# Sheet1.net
KiCad netlist of a schematic drawn in Altium Designer
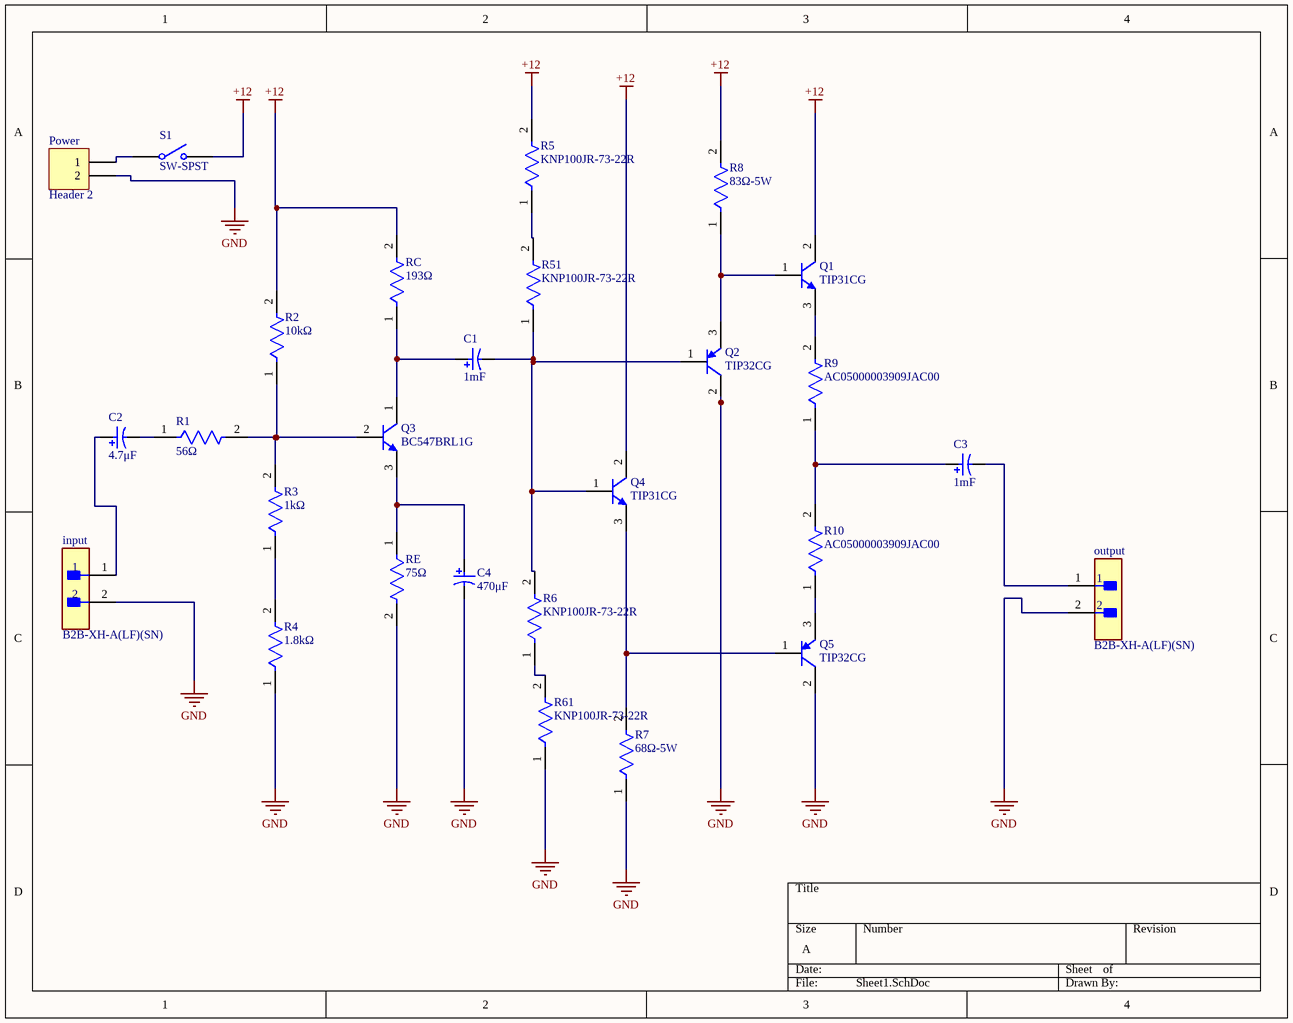
[diagram p0: Sheet1.SchDoc]

(export (version "E")
  (design (tool "Eeschema 10.0.6"))
  (components
    (comp (ref "C1")
      (value "1mF")
      (footprint "PNSC-EEU-EE2G100-2_V")
      (fields (field (name "PARTNUMBER") "EEU-EE2G100") (field (name "MANUFACTURER") "Panasonic"))
      (libsource (lib "Altium Content Vault") (part "PNSC-CAP-P-2"))
    )
    (comp (ref "C2")
      (value "4.7μF")
      (footprint "CAPPR55-200-1100X500X1200")
      (description "Aluminum Electrolytic Capacitor, 2.2 uF, +/- 20%, 50 V, -40 to 85 degC, 2-Pin THD, RoHS, Bulk")
      (fields (field (name "VOLTAGE") "50V") (field (name "MANUFACTURER") "Panasonic"))
      (libsource (lib "Altium Content Vault") (part "CAP-P-2"))
    )
    (comp (ref "C3")
      (value "1mF")
      (footprint "PNSC-EEU-EE2G100-2_V")
      (fields (field (name "PARTNUMBER") "EEU-EE2G100") (field (name "MANUFACTURER") "Panasonic"))
      (libsource (lib "Altium Content Vault") (part "PNSC-CAP-P-2"))
    )
    (comp (ref "C4")
      (value "470μF")
      (footprint "CAPPR55-200-1100X500X1200")
      (description "Aluminum Electrolytic Capacitor, 22 uF, +/- 20%, 50 V, -40 to 85 degC, 2-Pin THD, RoHS, Bulk")
      (fields (field (name "VOLTAGE") "50V") (field (name "MANUFACTURER") "Panasonic"))
      (libsource (lib "Altium Content Vault") (part "CAP-P-2"))
    )
    (comp (ref "input")
      (value "B2B-XH-A(LF)(SN)")
      (footprint "FP-B2B-XH-A_LF_SN-MFG")
      (description "CONN HEADER VERT 2POS 2.5MM")
      (libsource (lib "") (part "3bc925449376181038e59eaffc5286c_1"))
    )
    (comp (ref "output")
      (value "B2B-XH-A(LF)(SN)")
      (footprint "FP-B2B-XH-A_LF_SN-MFG")
      (description "CONN HEADER VERT 2POS 2.5MM")
      (libsource (lib "Altium Content Vault") (part "3bc925449376181038e59eaffc5286c"))
    )
    (comp (ref "Power")
      (value "Header 2")
      (footprint "HDR1X2")
      (description "Header, 2-Pin")
      (fields (field (name "PUBLISHER") "Altium Limited"))
      (libsource (lib "Miscellaneous Connectors") (part "Header 2"))
    )
    (comp (ref "Q1")
      (value "TIP31CG")
      (footprint "ONSC-TO-220-3-221A-09")
      (description "Complementary Silicon Plastic Power Transistor, 3-Pin TO-220, Pb-Free, Tube")
      (fields (field (name "MANUFACTURER") "On Semiconductor"))
      (libsource (lib "Altium Content Vault") (part "ONSC-NPN-B1C2E3-3_C"))
    )
    (comp (ref "Q2")
      (value "TIP32CG")
      (footprint "ONSC-TO-220-3-221A-09")
      (description "Complementary Silicon Plastic Power Transistor, 3-Pin TO-220, Pb-Free, Tube")
      (fields (field (name "MANUFACTURER") "On Semiconductor"))
      (libsource (lib "Altium Content Vault") (part "ONSC-PNP-B1C2E3-3"))
    )
    (comp (ref "Q3")
      (value "BC547BRL1G")
      (footprint "ONSC-TO-92-3-29-11_AM_BL")
      (description "Amplifier Transistor, NPN Silicon, 3-Pin TO-92, Pb-Free, Tape and Reel")
      (fields (field (name "MANUFACTURER") "On Semiconductor"))
      (libsource (lib "Altium Content Vault") (part "ONSC-NPN-C1B2E3-3"))
    )
    (comp (ref "Q4")
      (value "TIP31CG")
      (footprint "ONSC-TO-220-3-221A-09")
      (description "Complementary Silicon Plastic Power Transistor, 3-Pin TO-220, Pb-Free, Tube")
      (fields (field (name "MANUFACTURER") "On Semiconductor"))
      (libsource (lib "Altium Content Vault") (part "ONSC-NPN-B1C2E3-3_C"))
    )
    (comp (ref "Q5")
      (value "TIP32CG")
      (footprint "ONSC-TO-220-3-221A-09")
      (description "Complementary Silicon Plastic Power Transistor, 3-Pin TO-220, Pb-Free, Tube")
      (fields (field (name "MANUFACTURER") "On Semiconductor"))
      (libsource (lib "Altium Content Vault") (part "ONSC-PNP-B1C2E3-3"))
    )
    (comp (ref "R1")
      (value "56Ω")
      (footprint "FP-MRS25-MFG")
      (description "RES 1.1K OHM 0.6W 1% AXIAL")
      (fields
        (field (name "MANUFACTURER") "Vishay BC Components")
        (field (name "OCTOPART") "https://octopart.com/mrs25000c1101fct00-vishay-43740214")
      )
      (libsource (lib "Altium Content Vault") (part "1029c3af85768c4190bb7ad29bc67b5"))
    )
    (comp (ref "R2")
      (value "10kΩ")
      (footprint "FP-MRS25-MFG")
      (description "RES 1.1K OHM 0.6W 1% AXIAL")
      (fields
        (field (name "MANUFACTURER") "Vishay BC Components")
        (field (name "OCTOPART") "https://octopart.com/mrs25000c1101fct00-vishay-43740214")
      )
      (libsource (lib "Altium Content Vault") (part "1029c3af85768c4190bb7ad29bc67b5"))
    )
    (comp (ref "R3")
      (value "1kΩ")
      (footprint "FP-MRS25-MFG")
      (description "RES 1.1K OHM 0.6W 1% AXIAL")
      (fields
        (field (name "MANUFACTURER") "Vishay BC Components")
        (field (name "OCTOPART") "https://octopart.com/mrs25000c1101fct00-vishay-43740214")
      )
      (libsource (lib "Altium Content Vault") (part "1029c3af85768c4190bb7ad29bc67b5"))
    )
    (comp (ref "R4")
      (value "1.8kΩ")
      (footprint "FP-MRS25-MFG")
      (description "RES 1.1K OHM 0.6W 1% AXIAL")
      (fields
        (field (name "MANUFACTURER") "Vishay BC Components")
        (field (name "OCTOPART") "https://octopart.com/mrs25000c1101fct00-vishay-43740214")
      )
      (libsource (lib "Altium Content Vault") (part "1029c3af85768c4190bb7ad29bc67b5"))
    )
    (comp (ref "R5")
      (value "KNP100JR-73-22R")
      (footprint "FP-KNP100-MFG")
      (description "22 Ohms ±5% 1W Through Hole Resistor Axial Flame Retardant Coating, Safety Wirewound")
      (fields (field (name "OCTOPART") "https://octopart.com/knp100jr-73-22r-yageo-19031610"))
      (libsource (lib "Altium Content Vault") (part "1029c3af85768c4190bb7ad29bc67b5"))
    )
    (comp (ref "R6")
      (value "KNP100JR-73-22R")
      (footprint "FP-KNP100-MFG")
      (description "22 Ohms ±5% 1W Through Hole Resistor Axial Flame Retardant Coating, Safety Wirewound")
      (fields (field (name "OCTOPART") "https://octopart.com/knp100jr-73-22r-yageo-19031610"))
      (libsource (lib "Altium Content Vault") (part "1029c3af85768c4190bb7ad29bc67b5"))
    )
    (comp (ref "R7")
      (value "68Ω-5W")
      (footprint "FP-SQP500-MFG")
      (description "RES 1.2 OHM 5W 5% AXIAL")
      (fields
        (field (name "MANUFACTURER PART NUMBER") "SQP500JB-1R2")
        (field (name "OCTOPART") "https://octopart.com/sqp500jb-1r2-yageo-1162571")
      )
      (libsource (lib "Altium Content Vault") (part "1029c3af85768c4190bb7ad29bc67b5"))
    )
    (comp (ref "R8")
      (value "83Ω-5W")
      (footprint "FP-SQP500-MFG")
      (description "RES 1.2 OHM 5W 5% AXIAL")
      (fields
        (field (name "MANUFACTURER PART NUMBER") "SQP500JB-1R2")
        (field (name "OCTOPART") "https://octopart.com/sqp500jb-1r2-yageo-1162571")
      )
      (libsource (lib "Altium Content Vault") (part "1029c3af85768c4190bb7ad29bc67b5"))
    )
    (comp (ref "R9")
      (value "AC05000003909JAC00")
      (footprint "FP-AC05000003909JAC00-0")
      (description "RES 39 OHM 5W 5% AXIAL")
      (fields
        (field (name "OCTOPART") "https://octopart.com/ac05000003909jac00-vishay-39746279")
        (field (name "MANUFACTURER") "Vishay")
      )
      (libsource (lib "Altium Content Vault") (part "1029c3af85768c4190bb7ad29bc67b5"))
    )
    (comp (ref "R10")
      (value "AC05000003909JAC00")
      (footprint "FP-AC05000003909JAC00-0")
      (description "RES 39 OHM 5W 5% AXIAL")
      (fields
        (field (name "OCTOPART") "https://octopart.com/ac05000003909jac00-vishay-39746279")
        (field (name "MANUFACTURER") "Vishay")
      )
      (libsource (lib "Altium Content Vault") (part "1029c3af85768c4190bb7ad29bc67b5"))
    )
    (comp (ref "R51")
      (value "KNP100JR-73-22R")
      (footprint "FP-KNP100-MFG")
      (description "22 Ohms ±5% 1W Through Hole Resistor Axial Flame Retardant Coating, Safety Wirewound")
      (fields (field (name "OCTOPART") "https://octopart.com/knp100jr-73-22r-yageo-19031610"))
      (libsource (lib "Altium Content Vault") (part "1029c3af85768c4190bb7ad29bc67b5"))
    )
    (comp (ref "R61")
      (value "KNP100JR-73-22R")
      (footprint "FP-KNP100-MFG")
      (description "22 Ohms ±5% 1W Through Hole Resistor Axial Flame Retardant Coating, Safety Wirewound")
      (fields (field (name "OCTOPART") "https://octopart.com/knp100jr-73-22r-yageo-19031610"))
      (libsource (lib "Altium Content Vault") (part "1029c3af85768c4190bb7ad29bc67b5"))
    )
    (comp (ref "RC")
      (value "193Ω")
      (footprint "FP-MRS25-MFG")
      (description "RES 1.1K OHM 0.6W 1% AXIAL")
      (fields
        (field (name "MANUFACTURER") "Vishay BC Components")
        (field (name "OCTOPART") "https://octopart.com/mrs25000c1101fct00-vishay-43740214")
      )
      (libsource (lib "Altium Content Vault") (part "1029c3af85768c4190bb7ad29bc67b5"))
    )
    (comp (ref "RE")
      (value "75Ω")
      (footprint "FP-MRS25-MFG")
      (description "RES 1.1K OHM 0.6W 1% AXIAL")
      (fields
        (field (name "MANUFACTURER") "Vishay BC Components")
        (field (name "OCTOPART") "https://octopart.com/mrs25000c1101fct00-vishay-43740214")
      )
      (libsource (lib "Altium Content Vault") (part "1029c3af85768c4190bb7ad29bc67b5"))
    )
    (comp (ref "S1")
      (value "SW-SPST")
      (footprint "SPST-2")
      (description "Single-Pole, Single-Throw Switch")
      (fields (field (name "PUBLISHER") "Altium Limited"))
      (libsource (lib "Miscellaneous Devices") (part "SW-SPST"))
    )
  )
  (nets
    (net (code "1") (name "+12") (class "Default")
      (node (ref "Q1") (pin "2") (pinfunction "C_2") (pintype "passive"))
      (node (ref "Q4") (pin "2") (pinfunction "C_2") (pintype "passive"))
      (node (ref "R2") (pin "2") (pinfunction "2_2") (pintype "passive"))
      (node (ref "R5") (pin "2") (pinfunction "2_2") (pintype "passive"))
      (node (ref "R8") (pin "2") (pinfunction "2_2") (pintype "passive"))
      (node (ref "RC") (pin "2") (pinfunction "2_2") (pintype "passive"))
      (node (ref "S1") (pin "2") (pinfunction "NO_2") (pintype "passive"))
    )
    (net (code "2") (name "GND") (class "Default")
      (node (ref "C4") (pin "2") (pinfunction "2_2") (pintype "passive"))
      (node (ref "Power") (pin "2") (pinfunction "2_2") (pintype "passive"))
      (node (ref "Q2") (pin "2") (pinfunction "C_2") (pintype "passive"))
      (node (ref "Q5") (pin "2") (pinfunction "C_2") (pintype "passive"))
      (node (ref "R4") (pin "1") (pinfunction "1_1") (pintype "passive"))
      (node (ref "R61") (pin "1") (pinfunction "1_1") (pintype "passive"))
      (node (ref "R7") (pin "1") (pinfunction "1_1") (pintype "passive"))
      (node (ref "RE") (pin "2") (pinfunction "2_2") (pintype "passive"))
      (node (ref "input") (pin "2") (pinfunction "2_2") (pintype "passive"))
      (node (ref "output") (pin "2") (pinfunction "2_2") (pintype "passive"))
    )
    (net (code "3") (name "Net-(C2-Pad1)") (class "Default")
      (node (ref "C2") (pin "1") (pinfunction "1_1") (pintype "passive"))
      (node (ref "input") (pin "1") (pinfunction "1_1") (pintype "passive"))
    )
    (net (code "4") (name "Net-(C2-Pad2)") (class "Default")
      (node (ref "C2") (pin "2") (pinfunction "2_2") (pintype "passive"))
      (node (ref "R1") (pin "1") (pinfunction "1_1") (pintype "passive"))
    )
    (net (code "5") (name "Net-(C3-Pad1)") (class "Default")
      (node (ref "C3") (pin "1") (pinfunction "1_1") (pintype "passive"))
      (node (ref "R10") (pin "2") (pinfunction "2_2") (pintype "passive"))
      (node (ref "R9") (pin "1") (pinfunction "1_1") (pintype "passive"))
    )
    (net (code "6") (name "Net-(C3-Pad2)") (class "Default")
      (node (ref "C3") (pin "2") (pinfunction "2_2") (pintype "passive"))
      (node (ref "output") (pin "1") (pinfunction "1_1") (pintype "passive"))
    )
    (net (code "7") (name "Net-(Q1-B)") (class "Default")
      (node (ref "Q1") (pin "1") (pinfunction "B_1") (pintype "passive"))
      (node (ref "Q2") (pin "3") (pinfunction "E_3") (pintype "passive"))
      (node (ref "R8") (pin "1") (pinfunction "1_1") (pintype "passive"))
    )
    (net (code "8") (name "Net-(Q1-E)") (class "Default")
      (node (ref "Q1") (pin "3") (pinfunction "E_3") (pintype "passive"))
      (node (ref "R9") (pin "2") (pinfunction "2_2") (pintype "passive"))
    )
    (net (code "9") (name "Net-(Q2-B)") (class "Default")
      (node (ref "C1") (pin "2") (pinfunction "2_2") (pintype "passive"))
      (node (ref "Q2") (pin "1") (pinfunction "B_1") (pintype "passive"))
      (node (ref "Q4") (pin "1") (pinfunction "B_1") (pintype "passive"))
      (node (ref "R51") (pin "1") (pinfunction "1_1") (pintype "passive"))
      (node (ref "R6") (pin "2") (pinfunction "2_2") (pintype "passive"))
    )
    (net (code "10") (name "Net-(Q3-B)") (class "Default")
      (node (ref "Q3") (pin "2") (pinfunction "B_2") (pintype "passive"))
      (node (ref "R1") (pin "2") (pinfunction "2_2") (pintype "passive"))
      (node (ref "R2") (pin "1") (pinfunction "1_1") (pintype "passive"))
      (node (ref "R3") (pin "2") (pinfunction "2_2") (pintype "passive"))
    )
    (net (code "11") (name "Net-(Q3-C)") (class "Default")
      (node (ref "C1") (pin "1") (pinfunction "1_1") (pintype "passive"))
      (node (ref "Q3") (pin "1") (pinfunction "C_1") (pintype "passive"))
      (node (ref "RC") (pin "1") (pinfunction "1_1") (pintype "passive"))
    )
    (net (code "12") (name "Net-(Q3-E)") (class "Default")
      (node (ref "C4") (pin "1") (pinfunction "1_1") (pintype "passive"))
      (node (ref "Q3") (pin "3") (pinfunction "E_3") (pintype "passive"))
      (node (ref "RE") (pin "1") (pinfunction "1_1") (pintype "passive"))
    )
    (net (code "13") (name "Net-(Q4-E)") (class "Default")
      (node (ref "Q4") (pin "3") (pinfunction "E_3") (pintype "passive"))
      (node (ref "Q5") (pin "1") (pinfunction "B_1") (pintype "passive"))
      (node (ref "R7") (pin "2") (pinfunction "2_2") (pintype "passive"))
    )
    (net (code "14") (name "Net-(Q5-E)") (class "Default")
      (node (ref "Q5") (pin "3") (pinfunction "E_3") (pintype "passive"))
      (node (ref "R10") (pin "1") (pinfunction "1_1") (pintype "passive"))
    )
    (net (code "15") (name "Net-(R3-Pad1)") (class "Default")
      (node (ref "R3") (pin "1") (pinfunction "1_1") (pintype "passive"))
      (node (ref "R4") (pin "2") (pinfunction "2_2") (pintype "passive"))
    )
    (net (code "16") (name "Net-(R5-Pad1)") (class "Default")
      (node (ref "R5") (pin "1") (pinfunction "1_1") (pintype "passive"))
      (node (ref "R51") (pin "2") (pinfunction "2_2") (pintype "passive"))
    )
    (net (code "17") (name "Net-(R6-Pad1)") (class "Default")
      (node (ref "R6") (pin "1") (pinfunction "1_1") (pintype "passive"))
      (node (ref "R61") (pin "2") (pinfunction "2_2") (pintype "passive"))
    )
    (net (code "18") (name "Net-(S1-COMMON)") (class "Default")
      (node (ref "Power") (pin "1") (pinfunction "1_1") (pintype "passive"))
      (node (ref "S1") (pin "1") (pinfunction "COMMON_1") (pintype "passive"))
    )
  )
)
